# Mainboard.net
KiCad netlist of a schematic drawn in EAGLE
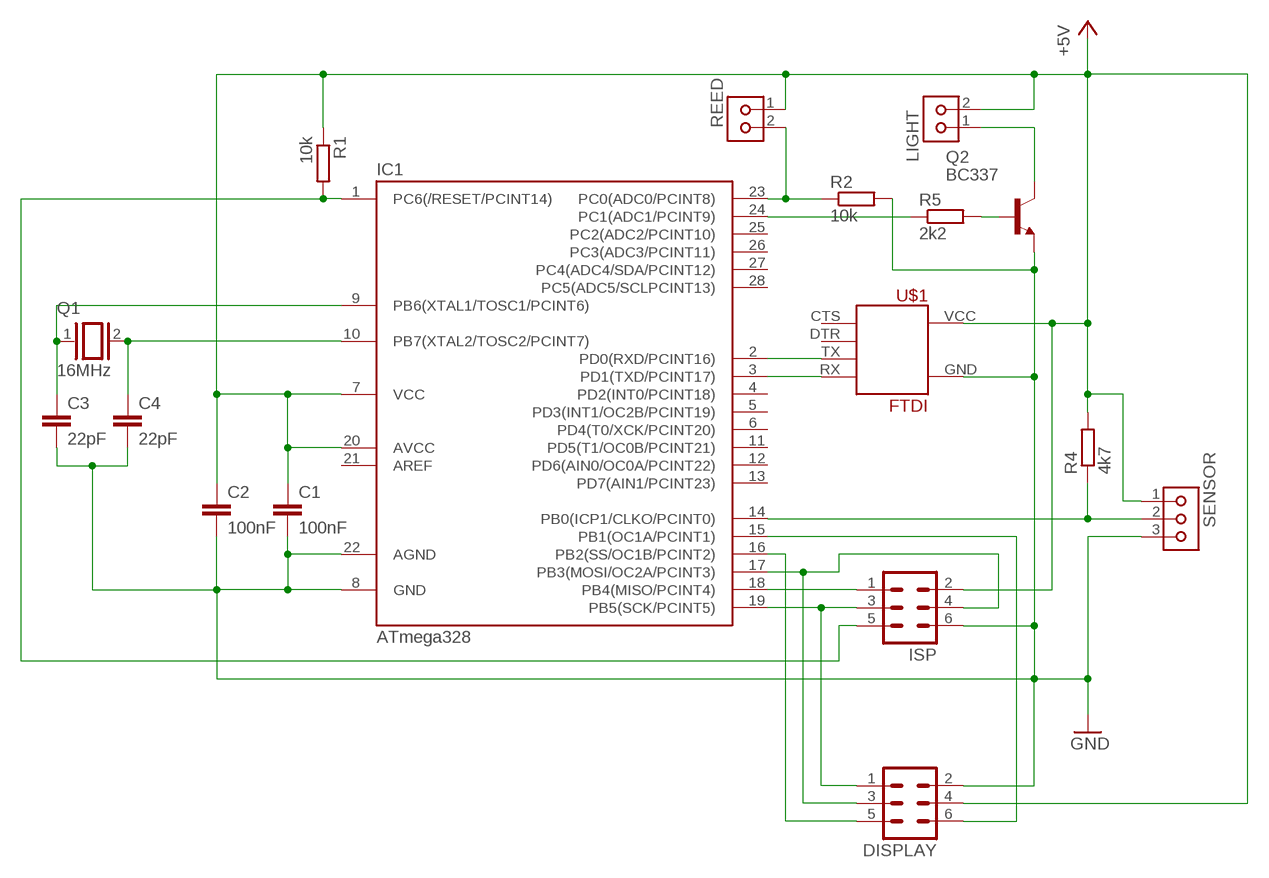
[diagram p0: schematic, sheet 1]

(export (version "E")
  (design (tool "Eeschema 10.0.6"))
  (components
    (comp (ref "C1")
      (value "100nF")
      (footprint "eagle-import:C050-025X075")
      (libsource (lib "eagle-import") (part "C-EU050-025X075"))
    )
    (comp (ref "C2")
      (value "100nF")
      (footprint "eagle-import:C025-025X050")
      (libsource (lib "eagle-import") (part "C-EU025-025X050"))
    )
    (comp (ref "C3")
      (value "22pF")
      (footprint "eagle-import:C025-025X050")
      (libsource (lib "eagle-import") (part "C-EU025-025X050"))
    )
    (comp (ref "C4")
      (value "22pF")
      (footprint "eagle-import:C025-025X050")
      (libsource (lib "eagle-import") (part "C-EU025-025X050"))
    )
    (comp (ref "DISPLAY")
      (value "ML6")
      (footprint "eagle-import:ML6")
      (libsource (lib "eagle-import") (part "ML6"))
    )
    (comp (ref "IC1")
      (value "ATmega328")
      (footprint "eagle-import:DIL28-3")
      (libsource (lib "eagle-import") (part "MEGA48/88/168-PU"))
    )
    (comp (ref "ISP")
      (value "ML6")
      (footprint "eagle-import:ML6")
      (libsource (lib "eagle-import") (part "ML6"))
    )
    (comp (ref "LIGHT")
      (value "KK2VSQ")
      (footprint "eagle-import:KK-V-2-SQ")
      (libsource (lib "eagle-import") (part "KK2VSQ"))
    )
    (comp (ref "Q1")
      (value "16MHz")
      (footprint "eagle-import:QS")
      (libsource (lib "eagle-import") (part "XTAL/S"))
    )
    (comp (ref "Q2")
      (value "BC337")
      (footprint "eagle-import:TO92-STRAIGHT-0.254")
      (libsource (lib "eagle-import") (part "BC337"))
    )
    (comp (ref "R1")
      (value "10k")
      (footprint "eagle-import:0207_10")
      (libsource (lib "eagle-import") (part "R-EU_0207/10"))
    )
    (comp (ref "R2")
      (value "10k")
      (footprint "eagle-import:0204V")
      (libsource (lib "eagle-import") (part "R-EU_0204/2V"))
    )
    (comp (ref "R4")
      (value "4k7")
      (footprint "eagle-import:0204_7")
      (libsource (lib "eagle-import") (part "R-EU_0204/7"))
    )
    (comp (ref "R5")
      (value "2k2")
      (footprint "eagle-import:0204_7")
      (libsource (lib "eagle-import") (part "R-EU_0204/7"))
    )
    (comp (ref "REED")
      (value "KK2VSQ")
      (footprint "eagle-import:KK-V-2-SQ")
      (libsource (lib "eagle-import") (part "KK2VSQ"))
    )
    (comp (ref "SENSOR")
      (value "KK3V")
      (footprint "eagle-import:KK-V-3")
      (libsource (lib "eagle-import") (part "KK3V"))
    )
    (comp (ref "U$1")
      (value "FTDI")
      (footprint "eagle-import:FTDI-1")
      (libsource (lib "eagle-import") (part "FTDI"))
    )
  )
  (nets
    (net (code "1") (name "+5V") (class "Default")
      (node (ref "C1") (pin "1") (pinfunction "1_1") (pintype "passive"))
      (node (ref "C2") (pin "1") (pinfunction "1_1") (pintype "passive"))
      (node (ref "DISPLAY") (pin "4") (pinfunction "4_4") (pintype "passive"))
      (node (ref "IC1") (pin "20") (pinfunction "AVCC_20") (pintype "passive"))
      (node (ref "IC1") (pin "7") (pinfunction "VCC_7") (pintype "power_in"))
      (node (ref "ISP") (pin "2") (pinfunction "2_2") (pintype "passive"))
      (node (ref "LIGHT") (pin "2") (pinfunction "2_2") (pintype "bidirectional"))
      (node (ref "R1") (pin "1") (pinfunction "1_1") (pintype "passive"))
      (node (ref "R4") (pin "2") (pinfunction "2_2") (pintype "passive"))
      (node (ref "REED") (pin "1") (pinfunction "1_1") (pintype "bidirectional"))
      (node (ref "SENSOR") (pin "1") (pinfunction "1_1") (pintype "bidirectional"))
      (node (ref "U$1") (pin "VCC") (pinfunction "+5V_VCC") (pintype "power_in"))
    )
    (net (code "2") (name "GND") (class "Default")
      (node (ref "C1") (pin "2") (pinfunction "2_2") (pintype "passive"))
      (node (ref "C2") (pin "2") (pinfunction "2_2") (pintype "passive"))
      (node (ref "C3") (pin "2") (pinfunction "2_2") (pintype "passive"))
      (node (ref "C4") (pin "2") (pinfunction "2_2") (pintype "passive"))
      (node (ref "DISPLAY") (pin "2") (pinfunction "2_2") (pintype "passive"))
      (node (ref "IC1") (pin "22") (pinfunction "AGND_22") (pintype "power_in"))
      (node (ref "IC1") (pin "8") (pinfunction "GND_8") (pintype "power_in"))
      (node (ref "ISP") (pin "6") (pinfunction "6_6") (pintype "passive"))
      (node (ref "Q2") (pin "3") (pinfunction "E_3") (pintype "passive"))
      (node (ref "R2") (pin "2") (pinfunction "2_2") (pintype "passive"))
      (node (ref "SENSOR") (pin "3") (pinfunction "3_3") (pintype "bidirectional"))
      (node (ref "U$1") (pin "GND") (pinfunction "GND_GND") (pintype "power_in"))
    )
    (net (code "3") (name "Net-(IC1-PB0(ICP1{slash}CLKO{slash}PCINT0))") (class "Default")
      (node (ref "IC1") (pin "14") (pinfunction "PB0(ICP1/CLKO/PCINT0)_14") (pintype "bidirectional"))
      (node (ref "R4") (pin "1") (pinfunction "1_1") (pintype "passive"))
      (node (ref "SENSOR") (pin "2") (pinfunction "2_2") (pintype "bidirectional"))
    )
    (net (code "4") (name "Net-(IC1-PB1(OC1A{slash}PCINT1))") (class "Default")
      (node (ref "DISPLAY") (pin "6") (pinfunction "6_6") (pintype "passive"))
      (node (ref "IC1") (pin "15") (pinfunction "PB1(OC1A/PCINT1)_15") (pintype "bidirectional"))
    )
    (net (code "5") (name "Net-(IC1-PB2(SS{slash}OC1B{slash}PCINT2))") (class "Default")
      (node (ref "DISPLAY") (pin "5") (pinfunction "5_5") (pintype "passive"))
      (node (ref "IC1") (pin "16") (pinfunction "PB2(SS/OC1B/PCINT2)_16") (pintype "bidirectional"))
    )
    (net (code "6") (name "Net-(IC1-PB3(MOSI{slash}OC2A{slash}PCINT3))") (class "Default")
      (node (ref "DISPLAY") (pin "3") (pinfunction "3_3") (pintype "passive"))
      (node (ref "IC1") (pin "17") (pinfunction "PB3(MOSI/OC2A/PCINT3)_17") (pintype "bidirectional"))
      (node (ref "ISP") (pin "4") (pinfunction "4_4") (pintype "passive"))
    )
    (net (code "7") (name "Net-(IC1-PB4(MISO{slash}PCINT4))") (class "Default")
      (node (ref "IC1") (pin "18") (pinfunction "PB4(MISO/PCINT4)_18") (pintype "bidirectional"))
      (node (ref "ISP") (pin "1") (pinfunction "1_1") (pintype "passive"))
    )
    (net (code "8") (name "Net-(IC1-PB5(SCK{slash}PCINT5))") (class "Default")
      (node (ref "DISPLAY") (pin "1") (pinfunction "1_1") (pintype "passive"))
      (node (ref "IC1") (pin "19") (pinfunction "PB5(SCK/PCINT5)_19") (pintype "bidirectional"))
      (node (ref "ISP") (pin "3") (pinfunction "3_3") (pintype "passive"))
    )
    (net (code "9") (name "Net-(IC1-PB6(XTAL1{slash}TOSC1{slash}PCINT6))") (class "Default")
      (node (ref "C3") (pin "1") (pinfunction "1_1") (pintype "passive"))
      (node (ref "IC1") (pin "9") (pinfunction "PB6(XTAL1/TOSC1/PCINT6)_9") (pintype "bidirectional"))
      (node (ref "Q1") (pin "1") (pinfunction "1_1") (pintype "passive"))
    )
    (net (code "10") (name "Net-(IC1-PB7(XTAL2{slash}TOSC2{slash}PCINT7))") (class "Default")
      (node (ref "C4") (pin "1") (pinfunction "1_1") (pintype "passive"))
      (node (ref "IC1") (pin "10") (pinfunction "PB7(XTAL2/TOSC2/PCINT7)_10") (pintype "bidirectional"))
      (node (ref "Q1") (pin "2") (pinfunction "2_2") (pintype "passive"))
    )
    (net (code "11") (name "Net-(IC1-PC0(ADC0{slash}PCINT8))") (class "Default")
      (node (ref "IC1") (pin "23") (pinfunction "PC0(ADC0/PCINT8)_23") (pintype "bidirectional"))
      (node (ref "R2") (pin "1") (pinfunction "1_1") (pintype "passive"))
      (node (ref "REED") (pin "2") (pinfunction "2_2") (pintype "bidirectional"))
    )
    (net (code "12") (name "Net-(IC1-PC1(ADC1{slash}PCINT9))") (class "Default")
      (node (ref "IC1") (pin "24") (pinfunction "PC1(ADC1/PCINT9)_24") (pintype "bidirectional"))
      (node (ref "R5") (pin "1") (pinfunction "1_1") (pintype "passive"))
    )
    (net (code "13") (name "Net-(IC1-PC6({slash}RESET{slash}PCINT14))") (class "Default")
      (node (ref "IC1") (pin "1") (pinfunction "PC6(/RESET/PCINT14)_1") (pintype "bidirectional"))
      (node (ref "ISP") (pin "5") (pinfunction "5_5") (pintype "passive"))
      (node (ref "R1") (pin "2") (pinfunction "2_2") (pintype "passive"))
    )
    (net (code "14") (name "Net-(IC1-PD0(RXD{slash}PCINT16))") (class "Default")
      (node (ref "IC1") (pin "2") (pinfunction "PD0(RXD/PCINT16)_2") (pintype "bidirectional"))
      (node (ref "U$1") (pin "TX") (pinfunction "TX_TX") (pintype "bidirectional"))
    )
    (net (code "15") (name "Net-(IC1-PD1(TXD{slash}PCINT17))") (class "Default")
      (node (ref "IC1") (pin "3") (pinfunction "PD1(TXD/PCINT17)_3") (pintype "bidirectional"))
      (node (ref "U$1") (pin "RX") (pinfunction "RX_RX") (pintype "bidirectional"))
    )
    (net (code "16") (name "Net-(Q2-B)") (class "Default")
      (node (ref "Q2") (pin "2") (pinfunction "B_2") (pintype "passive"))
      (node (ref "R5") (pin "2") (pinfunction "2_2") (pintype "passive"))
    )
    (net (code "17") (name "Net-(Q2-C)") (class "Default")
      (node (ref "LIGHT") (pin "1") (pinfunction "1_1") (pintype "bidirectional"))
      (node (ref "Q2") (pin "1") (pinfunction "C_1") (pintype "passive"))
    )
    (net (code "18") (name "unconnected-(IC1-AREF-Pad21)") (class "Default")
      (node (ref "IC1") (pin "21") (pinfunction "AREF_21") (pintype "passive"))
    )
    (net (code "19") (name "unconnected-(IC1-PC2(ADC2{slash}PCINT10)-Pad25)") (class "Default")
      (node (ref "IC1") (pin "25") (pinfunction "PC2(ADC2/PCINT10)_25") (pintype "bidirectional"))
    )
    (net (code "20") (name "unconnected-(IC1-PC3(ADC3{slash}PCINT11)-Pad26)") (class "Default")
      (node (ref "IC1") (pin "26") (pinfunction "PC3(ADC3/PCINT11)_26") (pintype "bidirectional"))
    )
    (net (code "21") (name "unconnected-(IC1-PC4(ADC4{slash}SDA{slash}PCINT12)-Pad27)") (class "Default")
      (node (ref "IC1") (pin "27") (pinfunction "PC4(ADC4/SDA/PCINT12)_27") (pintype "bidirectional"))
    )
    (net (code "22") (name "unconnected-(IC1-PC5(ADC5{slash}SCLPCINT13)-Pad28)") (class "Default")
      (node (ref "IC1") (pin "28") (pinfunction "PC5(ADC5/SCLPCINT13)_28") (pintype "bidirectional"))
    )
    (net (code "23") (name "unconnected-(IC1-PD2(INT0{slash}PCINT18)-Pad4)") (class "Default")
      (node (ref "IC1") (pin "4") (pinfunction "PD2(INT0/PCINT18)_4") (pintype "bidirectional"))
    )
    (net (code "24") (name "unconnected-(IC1-PD3(INT1{slash}OC2B{slash}PCINT19)-Pad5)") (class "Default")
      (node (ref "IC1") (pin "5") (pinfunction "PD3(INT1/OC2B/PCINT19)_5") (pintype "bidirectional"))
    )
    (net (code "25") (name "unconnected-(IC1-PD4(T0{slash}XCK{slash}PCINT20)-Pad6)") (class "Default")
      (node (ref "IC1") (pin "6") (pinfunction "PD4(T0/XCK/PCINT20)_6") (pintype "bidirectional"))
    )
    (net (code "26") (name "unconnected-(IC1-PD5(T1{slash}OC0B{slash}PCINT21)-Pad11)") (class "Default")
      (node (ref "IC1") (pin "11") (pinfunction "PD5(T1/OC0B/PCINT21)_11") (pintype "bidirectional"))
    )
    (net (code "27") (name "unconnected-(IC1-PD6(AIN0{slash}OC0A{slash}PCINT22)-Pad12)") (class "Default")
      (node (ref "IC1") (pin "12") (pinfunction "PD6(AIN0/OC0A/PCINT22)_12") (pintype "bidirectional"))
    )
    (net (code "28") (name "unconnected-(IC1-PD7(AIN1{slash}PCINT23)-Pad13)") (class "Default")
      (node (ref "IC1") (pin "13") (pinfunction "PD7(AIN1/PCINT23)_13") (pintype "bidirectional"))
    )
    (net (code "29") (name "unconnected-(U$1-PadCTS)") (class "Default")
      (node (ref "U$1") (pin "CTS") (pinfunction "CTS_CTS") (pintype "bidirectional"))
    )
    (net (code "30") (name "unconnected-(U$1-PadDTR)") (class "Default")
      (node (ref "U$1") (pin "DTR") (pinfunction "DTR_DTR") (pintype "bidirectional"))
    )
  )
)
